# usb-serial.net
KiCad netlist of a schematic drawn in Altium Designer
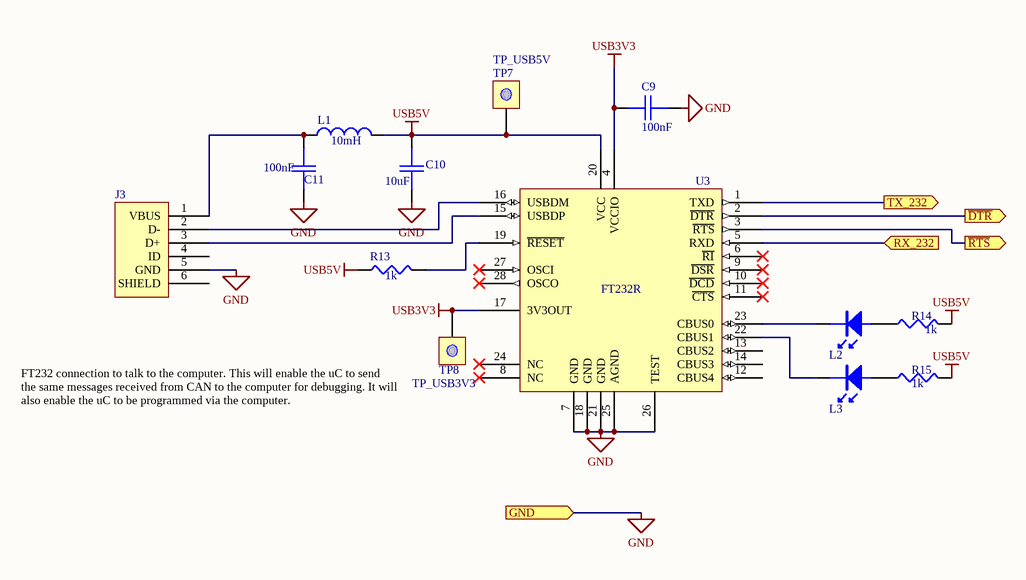
[diagram p0: usb-serial.SchDoc]

(export (version "E")
  (design (tool "Eeschema 10.0.6"))
  (components
    (comp (ref "C9")
      (value "100nF")
      (footprint "0603")
      (description "Capacitor")
      (fields (field (name "Comment") "CAP"))
      (libsource (lib "RCLDQ") (part "CAP"))
    )
    (comp (ref "C10")
      (value "10uF")
      (footprint "0603")
      (description "Capacitor")
      (fields (field (name "Comment") "CAP"))
      (libsource (lib "RCLDQ") (part "CAP"))
    )
    (comp (ref "C11")
      (value "100nF")
      (footprint "0603")
      (description "Capacitor")
      (fields (field (name "Comment") "CAP"))
      (libsource (lib "RCLDQ") (part "CAP"))
    )
    (comp (ref "J3")
      (value "USB_MINIB")
      (footprint "USBMINIB")
      (description "USB Mini B Connector")
      (libsource (lib "sion") (part "USB_miniB_SMT"))
    )
    (comp (ref "L1")
      (value "10mH")
      (footprint "1812")
      (description "Inductor")
      (fields
        (field (name "MANUFACTURER") "Generic Components")
        (field (name "Comment") "INDUCTOR")
        (field (name "PUBLISHER") "Altium Limited")
      )
      (libsource (lib "RCLDQ") (part "INDUCTOR"))
    )
    (comp (ref "L2") (value "LED") (footprint "0805LED") (libsource (lib "RCLDQ") (part "LED")))
    (comp (ref "L3") (value "LED") (footprint "0805LED") (libsource (lib "RCLDQ") (part "LED")))
    (comp (ref "R13")
      (value "1k")
      (footprint "0603")
      (description "Resistor")
      (fields (field (name "Comment") "RES1"))
      (libsource (lib "RCLDQ") (part "RES1"))
    )
    (comp (ref "R14")
      (value "1k")
      (footprint "0603")
      (description "Resistor")
      (fields (field (name "Comment") "RES1"))
      (libsource (lib "RCLDQ") (part "RES1"))
    )
    (comp (ref "R15")
      (value "1k")
      (footprint "0603")
      (description "Resistor")
      (fields (field (name "Comment") "RES1"))
      (libsource (lib "RCLDQ") (part "RES1"))
    )
    (comp (ref "TP7")
      (value "TP_USB5V")
      (footprint "TESTPOINT")
      (description "TEST POINT")
      (libsource (lib "Miscellaneous") (part "TEST"))
    )
    (comp (ref "TP8")
      (value "TP_USB3V3")
      (footprint "TESTPOINT")
      (description "TEST POINT")
      (libsource (lib "") (part "TEST_1"))
    )
    (comp (ref "U3")
      (value "FT232R")
      (footprint "SSOP28w")
      (libsource (lib "MiscellaneousIC") (part "FT232R"))
    )
  )
  (nets
    (net (code "1") (name "/RX_232") (class "Default")
      (node (ref "U3") (pin "5") (pinfunction "RXD_5") (pintype "input"))
    )
    (net (code "2") (name "/TX_232") (class "Default")
      (node (ref "U3") (pin "1") (pinfunction "TXD_1") (pintype "output"))
    )
    (net (code "3") (name "/~{DTR}") (class "Default")
      (node (ref "U3") (pin "2") (pinfunction "~{DTR}_2") (pintype "output"))
    )
    (net (code "4") (name "/~{RTS}") (class "Default")
      (node (ref "U3") (pin "3") (pinfunction "~{RTS}_3") (pintype "output"))
    )
    (net (code "5") (name "GND") (class "Default")
      (node (ref "C10") (pin "1") (pinfunction "1_1") (pintype "passive"))
      (node (ref "C11") (pin "2") (pinfunction "2_2") (pintype "passive"))
      (node (ref "C9") (pin "2") (pinfunction "2_2") (pintype "passive"))
      (node (ref "J3") (pin "5") (pinfunction "GND_5") (pintype "passive"))
      (node (ref "U3") (pin "18") (pinfunction "GND_18") (pintype "power_in"))
      (node (ref "U3") (pin "21") (pinfunction "GND_21") (pintype "power_in"))
      (node (ref "U3") (pin "25") (pinfunction "AGND_25") (pintype "power_in"))
      (node (ref "U3") (pin "26") (pinfunction "TEST_26") (pintype "passive"))
      (node (ref "U3") (pin "7") (pinfunction "GND_7") (pintype "power_in"))
    )
    (net (code "6") (name "Net-(J3-D+)") (class "Default")
      (node (ref "J3") (pin "3") (pinfunction "D+_3") (pintype "passive"))
      (node (ref "U3") (pin "15") (pinfunction "USBDP_15") (pintype "bidirectional"))
    )
    (net (code "7") (name "Net-(J3-D-)") (class "Default")
      (node (ref "J3") (pin "2") (pinfunction "D-_2") (pintype "passive"))
      (node (ref "U3") (pin "16") (pinfunction "USBDM_16") (pintype "bidirectional"))
    )
    (net (code "8") (name "Net-(J3-VBUS)") (class "Default")
      (node (ref "C11") (pin "1") (pinfunction "1_1") (pintype "passive"))
      (node (ref "J3") (pin "1") (pinfunction "VBUS_1") (pintype "passive"))
      (node (ref "L1") (pin "1") (pinfunction "1_1") (pintype "passive"))
    )
    (net (code "9") (name "Net-(L2-PadA)") (class "Default")
      (node (ref "L2") (pin "A") (pinfunction "A_A") (pintype "passive"))
      (node (ref "R14") (pin "1") (pinfunction "1_1") (pintype "passive"))
    )
    (net (code "10") (name "Net-(L3-PadA)") (class "Default")
      (node (ref "L3") (pin "A") (pinfunction "A_A") (pintype "passive"))
      (node (ref "R15") (pin "1") (pinfunction "1_1") (pintype "passive"))
    )
    (net (code "11") (name "Net-(U3-CBUS0)") (class "Default")
      (node (ref "L2") (pin "K") (pinfunction "K_K") (pintype "passive"))
      (node (ref "U3") (pin "23") (pinfunction "CBUS0_23") (pintype "bidirectional"))
    )
    (net (code "12") (name "Net-(U3-CBUS1)") (class "Default")
      (node (ref "L3") (pin "K") (pinfunction "K_K") (pintype "passive"))
      (node (ref "U3") (pin "22") (pinfunction "CBUS1_22") (pintype "bidirectional"))
    )
    (net (code "13") (name "Net-(U3-~{RESET})") (class "Default")
      (node (ref "R13") (pin "2") (pinfunction "2_2") (pintype "passive"))
      (node (ref "U3") (pin "19") (pinfunction "~{RESET}_19") (pintype "input"))
    )
    (net (code "14") (name "USB3V3") (class "Default")
      (node (ref "C9") (pin "1") (pinfunction "1_1") (pintype "passive"))
      (node (ref "TP8") (pin "0") (pinfunction "TP_0") (pintype "passive"))
      (node (ref "U3") (pin "17") (pinfunction "3V3OUT_17") (pintype "power_in"))
      (node (ref "U3") (pin "4") (pinfunction "VCCIO_4") (pintype "power_in"))
    )
    (net (code "15") (name "USB5V") (class "Default")
      (node (ref "C10") (pin "2") (pinfunction "2_2") (pintype "passive"))
      (node (ref "L1") (pin "2") (pinfunction "2_2") (pintype "passive"))
      (node (ref "R13") (pin "1") (pinfunction "1_1") (pintype "passive"))
      (node (ref "R14") (pin "2") (pinfunction "2_2") (pintype "passive"))
      (node (ref "R15") (pin "2") (pinfunction "2_2") (pintype "passive"))
      (node (ref "TP7") (pin "0") (pinfunction "TP_0") (pintype "passive"))
      (node (ref "U3") (pin "20") (pinfunction "VCC_20") (pintype "power_in"))
    )
    (net (code "16") (name "unconnected-(J3-ID-Pad4)") (class "Default")
      (node (ref "J3") (pin "4") (pinfunction "ID_4") (pintype "passive"))
    )
    (net (code "17") (name "unconnected-(J3-SHIELD-Pad6)") (class "Default")
      (node (ref "J3") (pin "6") (pinfunction "SHIELD_6") (pintype "passive"))
    )
    (net (code "18") (name "unconnected-(U3-CBUS2-Pad13)") (class "Default")
      (node (ref "U3") (pin "13") (pinfunction "CBUS2_13") (pintype "bidirectional"))
    )
    (net (code "19") (name "unconnected-(U3-CBUS3-Pad14)") (class "Default")
      (node (ref "U3") (pin "14") (pinfunction "CBUS3_14") (pintype "bidirectional"))
    )
    (net (code "20") (name "unconnected-(U3-CBUS4-Pad12)") (class "Default")
      (node (ref "U3") (pin "12") (pinfunction "CBUS4_12") (pintype "bidirectional"))
    )
    (net (code "21") (name "unconnected-(U3-NC-Pad8)") (class "Default")
      (node (ref "U3") (pin "8") (pinfunction "NC_8") (pintype "passive+no_connect"))
    )
    (net (code "22") (name "unconnected-(U3-NC-Pad24)") (class "Default")
      (node (ref "U3") (pin "24") (pinfunction "NC_24") (pintype "passive+no_connect"))
    )
    (net (code "23") (name "unconnected-(U3-OSCI-Pad27)") (class "Default")
      (node (ref "U3") (pin "27") (pinfunction "OSCI_27") (pintype "input+no_connect"))
    )
    (net (code "24") (name "unconnected-(U3-OSCO-Pad28)") (class "Default")
      (node (ref "U3") (pin "28") (pinfunction "OSCO_28") (pintype "output+no_connect"))
    )
    (net (code "25") (name "unconnected-(U3-~{CTS}-Pad11)") (class "Default")
      (node (ref "U3") (pin "11") (pinfunction "~{CTS}_11") (pintype "input+no_connect"))
    )
    (net (code "26") (name "unconnected-(U3-~{DCD}-Pad10)") (class "Default")
      (node (ref "U3") (pin "10") (pinfunction "~{DCD}_10") (pintype "input+no_connect"))
    )
    (net (code "27") (name "unconnected-(U3-~{DSR}-Pad9)") (class "Default")
      (node (ref "U3") (pin "9") (pinfunction "~{DSR}_9") (pintype "input+no_connect"))
    )
    (net (code "28") (name "unconnected-(U3-~{RI}-Pad6)") (class "Default")
      (node (ref "U3") (pin "6") (pinfunction "~{RI}_6") (pintype "input+no_connect"))
    )
  )
)
